# tb_project_arduino_pro_mini_proto_revA.net
KiCad netlist of a schematic drawn in EAGLE
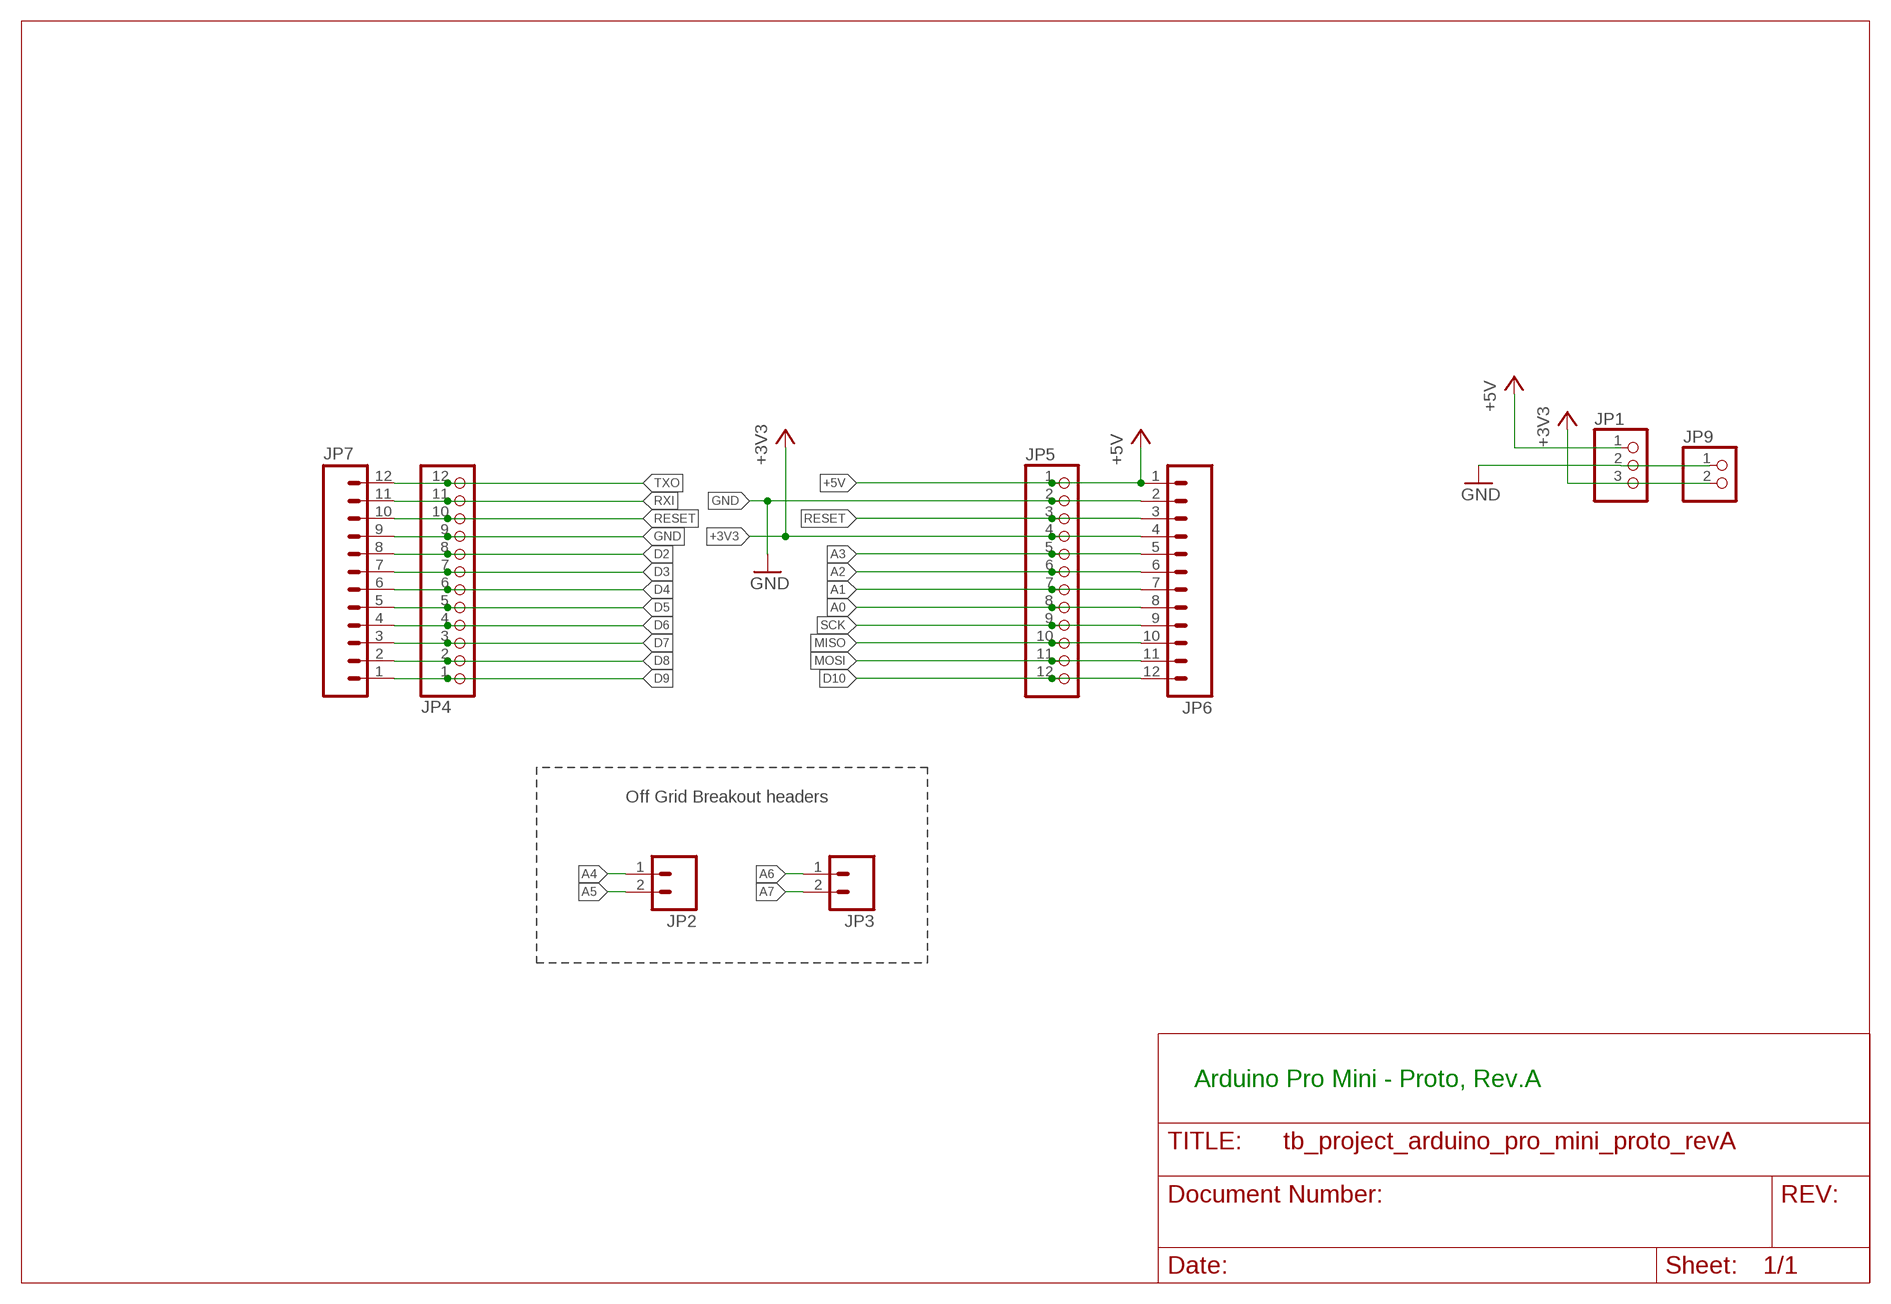
[diagram p0: schematic, sheet 1]

(export (version "E")
  (design (tool "Eeschema 10.0.6"))
  (components
    (comp (ref "JP1")
      (value "PINHD-1X3")
      (footprint "eagle-import:1X03")
      (libsource (lib "eagle-import") (part "PINHD-1X3"))
    )
    (comp (ref "JP2")
      (value "M02PTH")
      (footprint "eagle-import:1X02")
      (libsource (lib "eagle-import") (part "M02PTH"))
    )
    (comp (ref "JP3")
      (value "M02PTH")
      (footprint "eagle-import:1X02")
      (libsource (lib "eagle-import") (part "M02PTH"))
    )
    (comp (ref "JP4")
      (value "PINHD-1X12")
      (footprint "eagle-import:1X12")
      (libsource (lib "eagle-import") (part "PINHD-1X12"))
    )
    (comp (ref "JP5")
      (value "PINHD-1X12")
      (footprint "eagle-import:1X12")
      (libsource (lib "eagle-import") (part "PINHD-1X12"))
    )
    (comp (ref "JP6")
      (value "M12PTH")
      (footprint "eagle-import:1X12")
      (libsource (lib "eagle-import") (part "M12PTH"))
    )
    (comp (ref "JP7")
      (value "M12PTH")
      (footprint "eagle-import:1X12")
      (libsource (lib "eagle-import") (part "M12PTH"))
    )
    (comp (ref "JP9")
      (value "PINHD-1X2")
      (footprint "eagle-import:1X02")
      (libsource (lib "eagle-import") (part "PINHD-1X2"))
    )
  )
  (nets
    (net (code "1") (name "+3V3") (class "Default")
      (node (ref "JP1") (pin "3") (pinfunction "3_3") (pintype "passive"))
      (node (ref "JP5") (pin "4") (pinfunction "4_4") (pintype "passive"))
      (node (ref "JP6") (pin "4") (pinfunction "4_4") (pintype "passive"))
      (node (ref "JP9") (pin "2") (pinfunction "2_2") (pintype "passive"))
    )
    (net (code "2") (name "+5V") (class "Default")
      (node (ref "JP1") (pin "1") (pinfunction "1_1") (pintype "passive"))
      (node (ref "JP5") (pin "1") (pinfunction "1_1") (pintype "passive"))
      (node (ref "JP6") (pin "1") (pinfunction "1_1") (pintype "passive"))
    )
    (net (code "3") (name "A0") (class "Default")
      (node (ref "JP5") (pin "8") (pinfunction "8_8") (pintype "passive"))
      (node (ref "JP6") (pin "8") (pinfunction "8_8") (pintype "passive"))
    )
    (net (code "4") (name "A1") (class "Default")
      (node (ref "JP5") (pin "7") (pinfunction "7_7") (pintype "passive"))
      (node (ref "JP6") (pin "7") (pinfunction "7_7") (pintype "passive"))
    )
    (net (code "5") (name "A2") (class "Default")
      (node (ref "JP5") (pin "6") (pinfunction "6_6") (pintype "passive"))
      (node (ref "JP6") (pin "6") (pinfunction "6_6") (pintype "passive"))
    )
    (net (code "6") (name "A3") (class "Default")
      (node (ref "JP5") (pin "5") (pinfunction "5_5") (pintype "passive"))
      (node (ref "JP6") (pin "5") (pinfunction "5_5") (pintype "passive"))
    )
    (net (code "7") (name "A4") (class "Default")
      (node (ref "JP2") (pin "1") (pinfunction "1_1") (pintype "passive"))
    )
    (net (code "8") (name "A5") (class "Default")
      (node (ref "JP2") (pin "2") (pinfunction "2_2") (pintype "passive"))
    )
    (net (code "9") (name "A6") (class "Default")
      (node (ref "JP3") (pin "1") (pinfunction "1_1") (pintype "passive"))
    )
    (net (code "10") (name "A7") (class "Default")
      (node (ref "JP3") (pin "2") (pinfunction "2_2") (pintype "passive"))
    )
    (net (code "11") (name "D2") (class "Default")
      (node (ref "JP4") (pin "8") (pinfunction "8_8") (pintype "passive"))
      (node (ref "JP7") (pin "8") (pinfunction "8_8") (pintype "passive"))
    )
    (net (code "12") (name "D3") (class "Default")
      (node (ref "JP4") (pin "7") (pinfunction "7_7") (pintype "passive"))
      (node (ref "JP7") (pin "7") (pinfunction "7_7") (pintype "passive"))
    )
    (net (code "13") (name "D4") (class "Default")
      (node (ref "JP4") (pin "6") (pinfunction "6_6") (pintype "passive"))
      (node (ref "JP7") (pin "6") (pinfunction "6_6") (pintype "passive"))
    )
    (net (code "14") (name "D5") (class "Default")
      (node (ref "JP4") (pin "5") (pinfunction "5_5") (pintype "passive"))
      (node (ref "JP7") (pin "5") (pinfunction "5_5") (pintype "passive"))
    )
    (net (code "15") (name "D6") (class "Default")
      (node (ref "JP4") (pin "4") (pinfunction "4_4") (pintype "passive"))
      (node (ref "JP7") (pin "4") (pinfunction "4_4") (pintype "passive"))
    )
    (net (code "16") (name "D7") (class "Default")
      (node (ref "JP4") (pin "3") (pinfunction "3_3") (pintype "passive"))
      (node (ref "JP7") (pin "3") (pinfunction "3_3") (pintype "passive"))
    )
    (net (code "17") (name "D8") (class "Default")
      (node (ref "JP4") (pin "2") (pinfunction "2_2") (pintype "passive"))
      (node (ref "JP7") (pin "2") (pinfunction "2_2") (pintype "passive"))
    )
    (net (code "18") (name "D9") (class "Default")
      (node (ref "JP4") (pin "1") (pinfunction "1_1") (pintype "passive"))
      (node (ref "JP7") (pin "1") (pinfunction "1_1") (pintype "passive"))
    )
    (net (code "19") (name "D10") (class "Default")
      (node (ref "JP5") (pin "12") (pinfunction "12_12") (pintype "passive"))
      (node (ref "JP6") (pin "12") (pinfunction "12_12") (pintype "passive"))
    )
    (net (code "20") (name "GND") (class "Default")
      (node (ref "JP1") (pin "2") (pinfunction "2_2") (pintype "passive"))
      (node (ref "JP4") (pin "9") (pinfunction "9_9") (pintype "passive"))
      (node (ref "JP5") (pin "2") (pinfunction "2_2") (pintype "passive"))
      (node (ref "JP6") (pin "2") (pinfunction "2_2") (pintype "passive"))
      (node (ref "JP7") (pin "9") (pinfunction "9_9") (pintype "passive"))
      (node (ref "JP9") (pin "1") (pinfunction "1_1") (pintype "passive"))
    )
    (net (code "21") (name "MISO") (class "Default")
      (node (ref "JP5") (pin "10") (pinfunction "10_10") (pintype "passive"))
      (node (ref "JP6") (pin "10") (pinfunction "10_10") (pintype "passive"))
    )
    (net (code "22") (name "MOSI") (class "Default")
      (node (ref "JP5") (pin "11") (pinfunction "11_11") (pintype "passive"))
      (node (ref "JP6") (pin "11") (pinfunction "11_11") (pintype "passive"))
    )
    (net (code "23") (name "RESET") (class "Default")
      (node (ref "JP4") (pin "10") (pinfunction "10_10") (pintype "passive"))
      (node (ref "JP5") (pin "3") (pinfunction "3_3") (pintype "passive"))
      (node (ref "JP6") (pin "3") (pinfunction "3_3") (pintype "passive"))
      (node (ref "JP7") (pin "10") (pinfunction "10_10") (pintype "passive"))
    )
    (net (code "24") (name "RXI") (class "Default")
      (node (ref "JP4") (pin "11") (pinfunction "11_11") (pintype "passive"))
      (node (ref "JP7") (pin "11") (pinfunction "11_11") (pintype "passive"))
    )
    (net (code "25") (name "SCK") (class "Default")
      (node (ref "JP5") (pin "9") (pinfunction "9_9") (pintype "passive"))
      (node (ref "JP6") (pin "9") (pinfunction "9_9") (pintype "passive"))
    )
    (net (code "26") (name "TXO") (class "Default")
      (node (ref "JP4") (pin "12") (pinfunction "12_12") (pintype "passive"))
      (node (ref "JP7") (pin "12") (pinfunction "12_12") (pintype "passive"))
    )
  )
)
